# Sheet.net
KiCad netlist of a schematic drawn in Altium Designer
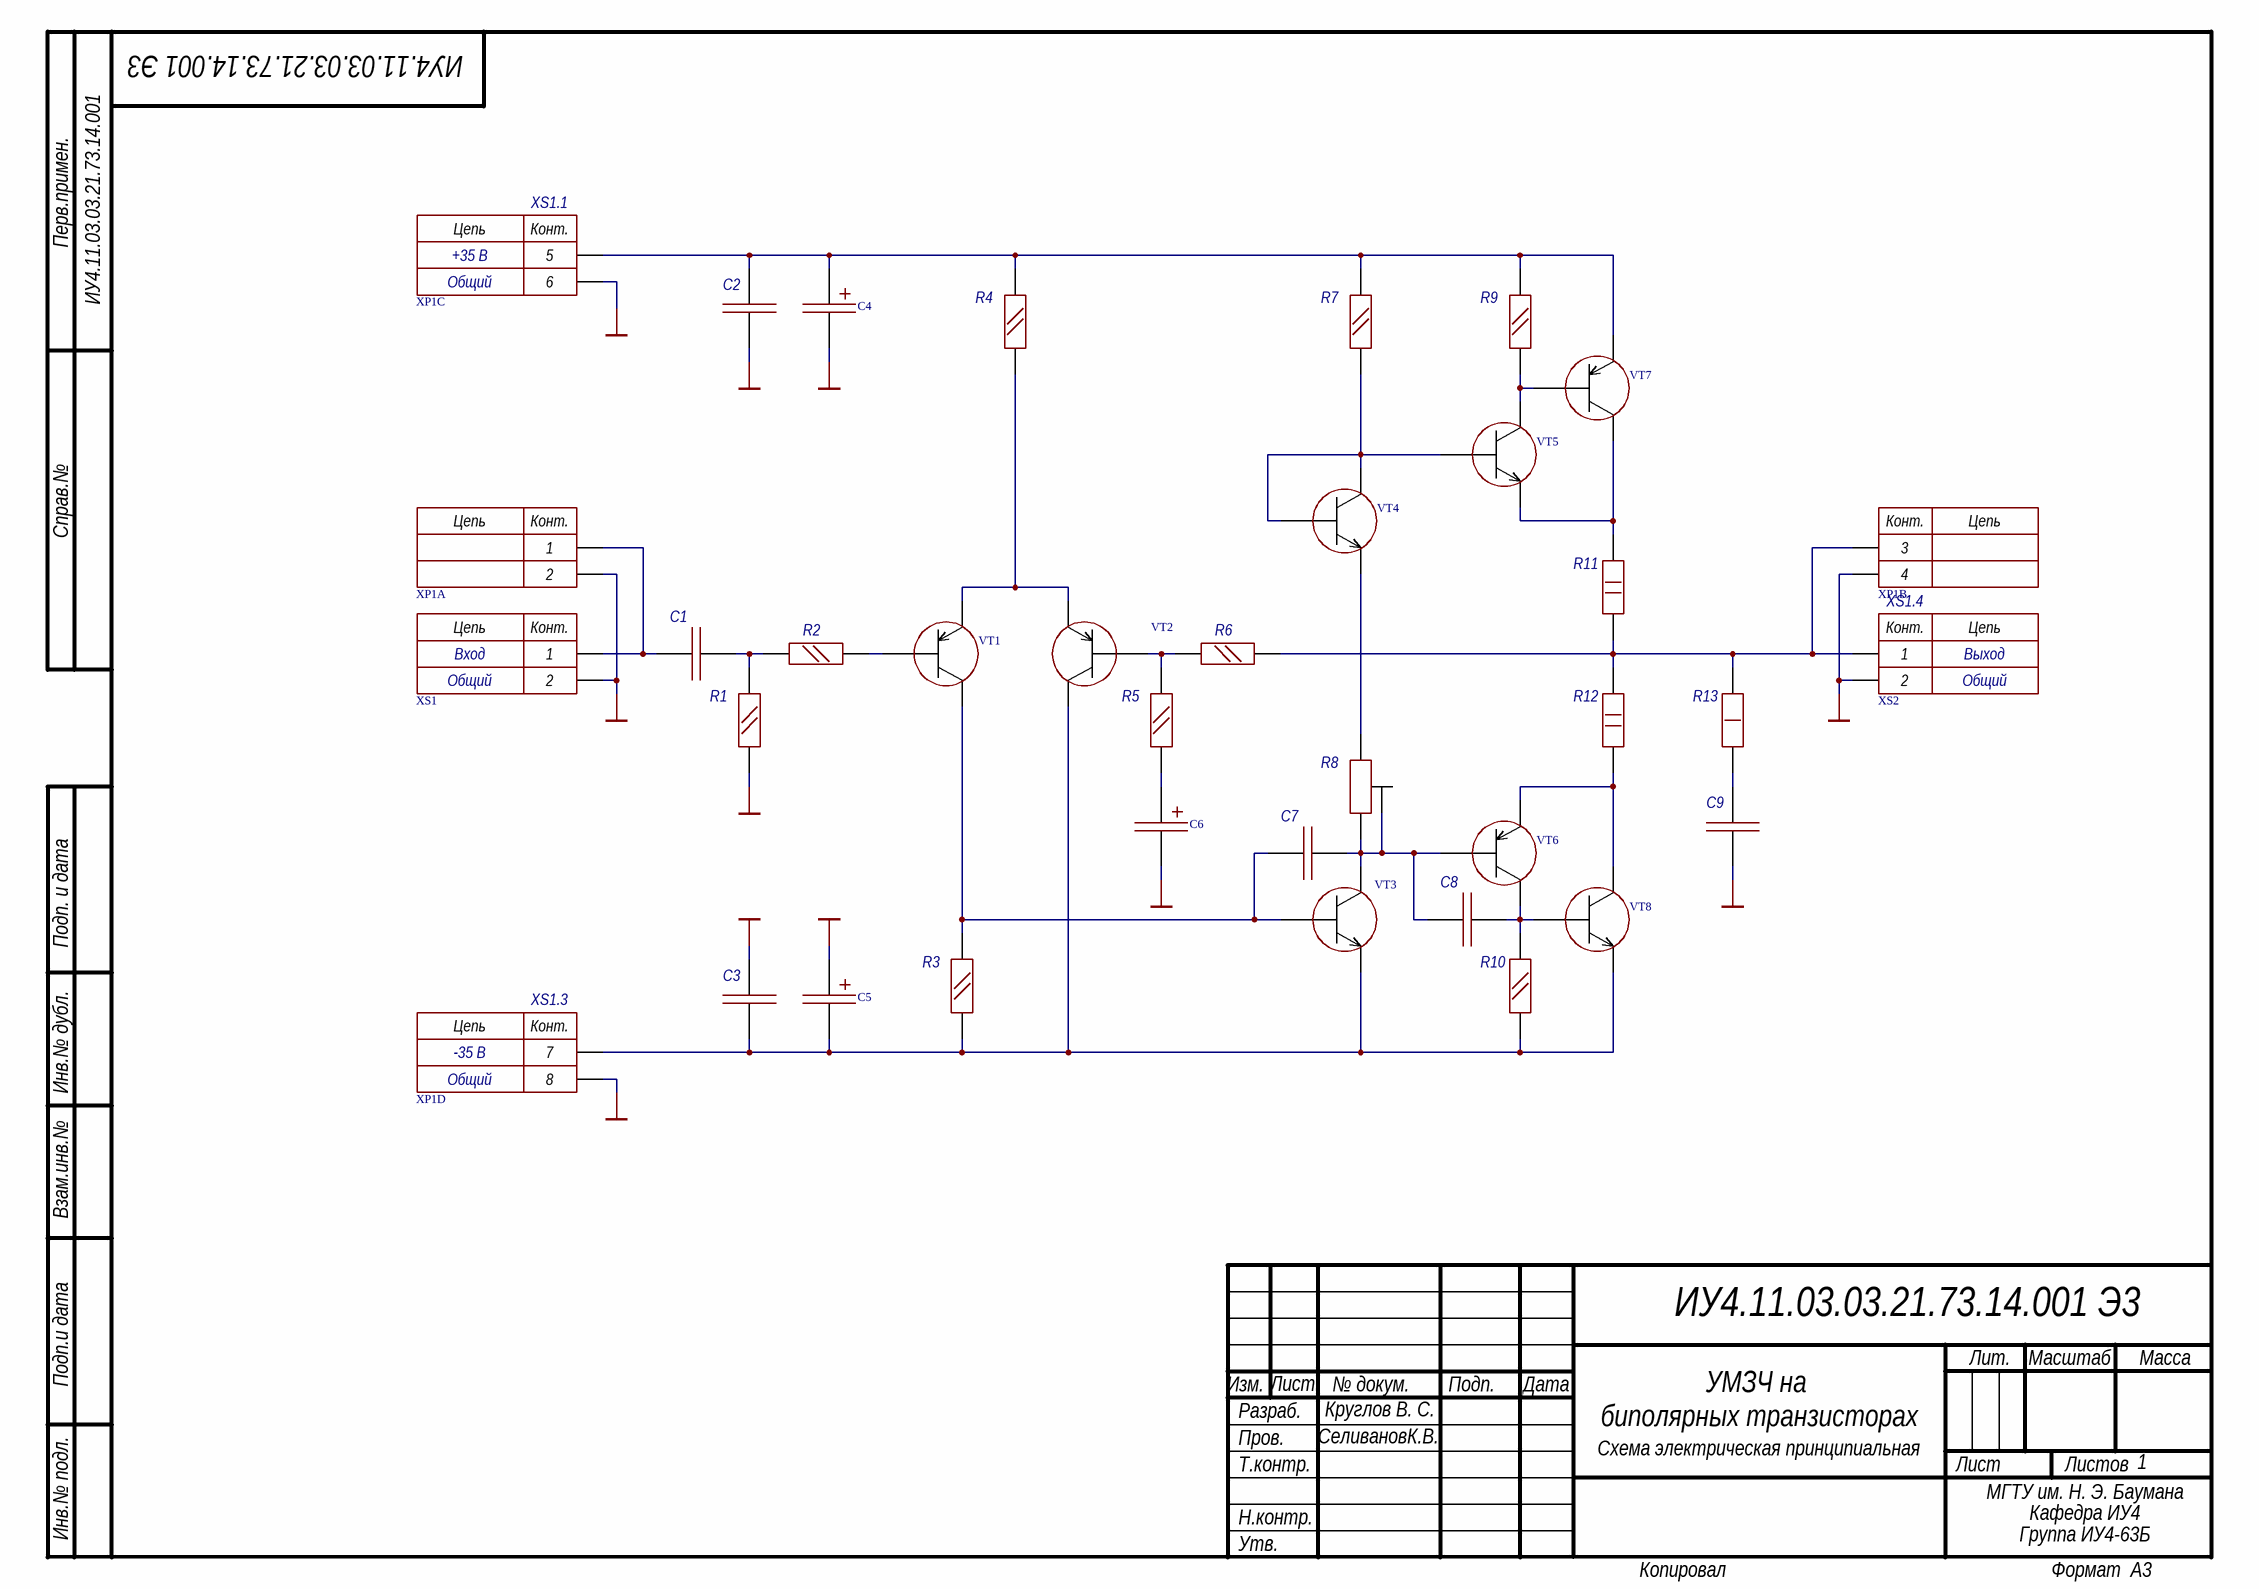
[diagram p0: Sheet.SchDoc]

(export (version "E")
  (design (tool "Eeschema 10.0.6"))
  (components
    (comp (ref "C1")
      (value "Capacitor")
      (footprint "C_PLY_10X5")
      (libsource (lib "Components - 07.07.24 - 20.56") (part "Capacitor"))
    )
    (comp (ref "C2")
      (value "Capacitor")
      (footprint "C_PLY_10X5")
      (libsource (lib "Components - 07.07.24 - 20.56") (part "Capacitor"))
    )
    (comp (ref "C3")
      (value "Capacitor")
      (footprint "C_PLY_10X5")
      (libsource (lib "Components - 07.07.24 - 20.56") (part "Capacitor"))
    )
    (comp (ref "C4")
      (value "Capactor polar")
      (footprint "C_EL_12X25")
      (libsource (lib "Components - 07.07.24 - 20.56") (part "Capactor polar"))
    )
    (comp (ref "C5")
      (value "Capactor polar")
      (footprint "C_EL_12X25")
      (libsource (lib "Components - 07.07.24 - 20.56") (part "Capactor polar"))
    )
    (comp (ref "C6")
      (value "Capactor polar")
      (footprint "C_EL_4X7")
      (libsource (lib "Components - 07.07.24 - 20.56") (part "Capactor polar"))
    )
    (comp (ref "C7")
      (value "Capacitor")
      (footprint "C_PLY_7X5")
      (libsource (lib "Components - 07.07.24 - 20.56") (part "Capacitor"))
    )
    (comp (ref "C8")
      (value "Capacitor")
      (footprint "C_PLY_7X5")
      (libsource (lib "Components - 07.07.24 - 20.56") (part "Capacitor"))
    )
    (comp (ref "C9")
      (value "Capacitor")
      (footprint "C_PLY_10X5")
      (libsource (lib "Components - 07.07.24 - 20.56") (part "Capacitor"))
    )
    (comp (ref "R1")
      (value "Res")
      (footprint "R0125W_AX025")
      (libsource (lib "Integrated_Library_PAAF") (part "Res"))
    )
    (comp (ref "R2") (value "Res") (footprint "R0125W_AX025") (libsource (lib "") (part "Res_1")))
    (comp (ref "R3")
      (value "Res")
      (footprint "R0125W_AX025")
      (libsource (lib "Integrated_Library_PAAF") (part "Res"))
    )
    (comp (ref "R4")
      (value "Res")
      (footprint "R0125W_AX025")
      (libsource (lib "Integrated_Library_PAAF") (part "Res"))
    )
    (comp (ref "R5")
      (value "Res")
      (footprint "R0125W_AX025")
      (libsource (lib "Integrated_Library_PAAF") (part "Res"))
    )
    (comp (ref "R6") (value "Res") (footprint "R0125W_AX025") (libsource (lib "") (part "Res_1")))
    (comp (ref "R7")
      (value "Res")
      (footprint "R0125W_AX025")
      (libsource (lib "Integrated_Library_PAAF") (part "Res"))
    )
    (comp (ref "R8")
      (value "POT")
      (footprint "POT_3296W")
      (libsource (lib "Integrated_Library_PAAF") (part "POT"))
    )
    (comp (ref "R9")
      (value "Res")
      (footprint "R0125W_AX025")
      (libsource (lib "Integrated_Library_PAAF") (part "Res"))
    )
    (comp (ref "R10")
      (value "Res")
      (footprint "R0125W_AX025")
      (libsource (lib "Integrated_Library_PAAF") (part "Res"))
    )
    (comp (ref "R11")
      (value "Res")
      (footprint "R2W_AX08")
      (libsource (lib "Integrated_Library_PAAF") (part "Res"))
    )
    (comp (ref "R12")
      (value "Res")
      (footprint "R2W_AX08")
      (libsource (lib "Integrated_Library_PAAF") (part "Res"))
    )
    (comp (ref "R13")
      (value "Res")
      (footprint "R1W_AX06")
      (libsource (lib "Integrated_Library_PAAF") (part "Res"))
    )
    (comp (ref "VT1")
      (value "Transistor_PNP")
      (footprint "TO92_3")
      (libsource (lib "Components - 07.07.24 - 21.07") (part "Transistor_PNP"))
    )
    (comp (ref "VT2")
      (value "Transistor_PNP")
      (footprint "TO92_3")
      (libsource (lib "Components - 07.07.24 - 21.07") (part "Transistor_PNP"))
    )
    (comp (ref "VT3")
      (value "BD139G")
      (footprint "TO220_3")
      (libsource (lib "Components - 07.07.24 - 21.07") (part "Transistor_NPN"))
    )
    (comp (ref "VT4")
      (value "BD139G")
      (footprint "TO126_3")
      (libsource (lib "Components - 07.07.24 - 21.07") (part "Transistor_NPN"))
    )
    (comp (ref "VT5")
      (value "BD139G")
      (footprint "TO126_3")
      (libsource (lib "Components - 07.07.24 - 21.07") (part "Transistor_NPN"))
    )
    (comp (ref "VT6")
      (value "Transistor_PNP")
      (footprint "TO126_3")
      (libsource (lib "Components - 07.07.24 - 21.07") (part "Transistor_PNP"))
    )
    (comp (ref "VT7")
      (value "Transistor_PNP")
      (footprint "TO247_3")
      (libsource (lib "Components - 07.07.24 - 21.07") (part "Transistor_PNP"))
    )
    (comp (ref "VT8")
      (value "BD139G")
      (footprint "TO247_3")
      (libsource (lib "Components - 07.07.24 - 21.07") (part "Transistor_NPN"))
    )
    (comp (ref "XP1")
      (value "CONN")
      (footprint "HDRR_F_2X4")
      (libsource (lib "Components - 07.07.24 - 20.56") (part "CONN"))
    )
    (comp (ref "XS1")
      (value "Audio")
      (footprint "FP-NMJ4HFD2-MFG")
      (libsource (lib "Integrated_Library_PAAF") (part "Audio"))
    )
    (comp (ref "XS2")
      (value "Audio")
      (footprint "FP-NMJ4HFD2-MFG")
      (libsource (lib "Integrated_Library_PAAF") (part "Audio"))
    )
  )
  (nets
    (net (code "1") (name "GND") (class "Default")
      (node (ref "C2") (pin "2") (pinfunction "2_2") (pintype "passive"))
      (node (ref "C3") (pin "2") (pinfunction "2_2") (pintype "passive"))
      (node (ref "C4") (pin "1") (pinfunction "1_1") (pintype "passive"))
      (node (ref "C5") (pin "2") (pinfunction "2_2") (pintype "passive"))
      (node (ref "C6") (pin "1") (pinfunction "1_1") (pintype "passive"))
      (node (ref "C9") (pin "2") (pinfunction "2_2") (pintype "passive"))
      (node (ref "R1") (pin "1") (pinfunction "1_1") (pintype "passive"))
      (node (ref "XP1") (pin "2") (pintype "passive"))
      (node (ref "XP1") (pin "4") (pintype "passive"))
      (node (ref "XP1") (pin "6") (pintype "passive"))
      (node (ref "XP1") (pin "8") (pintype "passive"))
      (node (ref "XS1") (pin "2") (pintype "passive"))
      (node (ref "XS2") (pin "2") (pintype "passive"))
    )
    (net (code "2") (name "Net-(C1-Pad1)") (class "Default")
      (node (ref "C1") (pin "1") (pinfunction "1_1") (pintype "passive"))
      (node (ref "XP1") (pin "1") (pintype "passive"))
      (node (ref "XS1") (pin "1") (pintype "passive"))
    )
    (net (code "3") (name "Net-(C1-Pad2)") (class "Default")
      (node (ref "C1") (pin "2") (pinfunction "2_2") (pintype "passive"))
      (node (ref "R1") (pin "2") (pinfunction "2_2") (pintype "passive"))
      (node (ref "R2") (pin "2") (pinfunction "2_2") (pintype "passive"))
    )
    (net (code "4") (name "Net-(C6-Pad2)") (class "Default")
      (node (ref "C6") (pin "2") (pinfunction "2_2") (pintype "passive"))
      (node (ref "R5") (pin "1") (pinfunction "1_1") (pintype "passive"))
    )
    (net (code "5") (name "Net-(C9-Pad1)") (class "Default")
      (node (ref "C9") (pin "1") (pinfunction "1_1") (pintype "passive"))
      (node (ref "R13") (pin "1") (pinfunction "1_1") (pintype "passive"))
    )
    (net (code "6") (name "Net-(R11-Pad1)") (class "Default")
      (node (ref "R11") (pin "1") (pinfunction "1_1") (pintype "passive"))
      (node (ref "R12") (pin "2") (pinfunction "2_2") (pintype "passive"))
      (node (ref "R13") (pin "2") (pinfunction "2_2") (pintype "passive"))
      (node (ref "R6") (pin "1") (pinfunction "1_1") (pintype "passive"))
      (node (ref "XP1") (pin "3") (pintype "passive"))
      (node (ref "XS2") (pin "1") (pintype "passive"))
    )
    (net (code "7") (name "Net-(VT1-B)") (class "Default")
      (node (ref "R2") (pin "1") (pinfunction "1_1") (pintype "passive"))
      (node (ref "VT1") (pin "3") (pinfunction "B_3") (pintype "passive"))
    )
    (net (code "8") (name "Net-(VT1-C)") (class "Default")
      (node (ref "C7") (pin "1") (pinfunction "1_1") (pintype "passive"))
      (node (ref "R3") (pin "2") (pinfunction "2_2") (pintype "passive"))
      (node (ref "VT1") (pin "2") (pinfunction "C_2") (pintype "passive"))
      (node (ref "VT3") (pin "3") (pinfunction "B_3") (pintype "passive"))
    )
    (net (code "9") (name "Net-(VT1-E)") (class "Default")
      (node (ref "R4") (pin "1") (pinfunction "1_1") (pintype "passive"))
      (node (ref "VT1") (pin "1") (pinfunction "E_1") (pintype "passive"))
      (node (ref "VT2") (pin "1") (pinfunction "E_1") (pintype "passive"))
    )
    (net (code "10") (name "Net-(VT2-B)") (class "Default")
      (node (ref "R5") (pin "2") (pinfunction "2_2") (pintype "passive"))
      (node (ref "R6") (pin "2") (pinfunction "2_2") (pintype "passive"))
      (node (ref "VT2") (pin "3") (pinfunction "B_3") (pintype "passive"))
    )
    (net (code "11") (name "Net-(VT2-C)") (class "Default")
      (node (ref "C3") (pin "1") (pinfunction "1_1") (pintype "passive"))
      (node (ref "C5") (pin "1") (pinfunction "1_1") (pintype "passive"))
      (node (ref "R10") (pin "1") (pinfunction "1_1") (pintype "passive"))
      (node (ref "R3") (pin "1") (pinfunction "1_1") (pintype "passive"))
      (node (ref "VT2") (pin "2") (pinfunction "C_2") (pintype "passive"))
      (node (ref "VT3") (pin "1") (pinfunction "E_1") (pintype "passive"))
      (node (ref "VT8") (pin "1") (pinfunction "E_1") (pintype "passive"))
      (node (ref "XP1") (pin "7") (pintype "passive"))
    )
    (net (code "12") (name "Net-(VT3-C)") (class "Default")
      (node (ref "C7") (pin "2") (pinfunction "2_2") (pintype "passive"))
      (node (ref "C8") (pin "1") (pinfunction "1_1") (pintype "passive"))
      (node (ref "R8") (pin "2") (pinfunction "2_2") (pintype "passive"))
      (node (ref "R8") (pin "3") (pinfunction "3_3") (pintype "passive"))
      (node (ref "VT3") (pin "2") (pinfunction "C_2") (pintype "passive"))
      (node (ref "VT6") (pin "3") (pinfunction "B_3") (pintype "passive"))
    )
    (net (code "13") (name "Net-(VT4-B)") (class "Default")
      (node (ref "R7") (pin "1") (pinfunction "1_1") (pintype "passive"))
      (node (ref "VT4") (pin "2") (pinfunction "C_2") (pintype "passive"))
      (node (ref "VT4") (pin "3") (pinfunction "B_3") (pintype "passive"))
      (node (ref "VT5") (pin "3") (pinfunction "B_3") (pintype "passive"))
    )
    (net (code "14") (name "Net-(VT4-E)") (class "Default")
      (node (ref "R8") (pin "1") (pinfunction "1_1") (pintype "passive"))
      (node (ref "VT4") (pin "1") (pinfunction "E_1") (pintype "passive"))
    )
    (net (code "15") (name "Net-(VT5-C)") (class "Default")
      (node (ref "R9") (pin "1") (pinfunction "1_1") (pintype "passive"))
      (node (ref "VT5") (pin "2") (pinfunction "C_2") (pintype "passive"))
      (node (ref "VT7") (pin "3") (pinfunction "B_3") (pintype "passive"))
    )
    (net (code "16") (name "Net-(VT5-E)") (class "Default")
      (node (ref "R11") (pin "2") (pinfunction "2_2") (pintype "passive"))
      (node (ref "VT5") (pin "1") (pinfunction "E_1") (pintype "passive"))
      (node (ref "VT7") (pin "2") (pinfunction "C_2") (pintype "passive"))
    )
    (net (code "17") (name "Net-(VT6-C)") (class "Default")
      (node (ref "C8") (pin "2") (pinfunction "2_2") (pintype "passive"))
      (node (ref "R10") (pin "2") (pinfunction "2_2") (pintype "passive"))
      (node (ref "VT6") (pin "2") (pinfunction "C_2") (pintype "passive"))
      (node (ref "VT8") (pin "3") (pinfunction "B_3") (pintype "passive"))
    )
    (net (code "18") (name "Net-(VT6-E)") (class "Default")
      (node (ref "R12") (pin "1") (pinfunction "1_1") (pintype "passive"))
      (node (ref "VT6") (pin "1") (pinfunction "E_1") (pintype "passive"))
      (node (ref "VT8") (pin "2") (pinfunction "C_2") (pintype "passive"))
    )
    (net (code "19") (name "Net-(VT7-E)") (class "Default")
      (node (ref "C2") (pin "1") (pinfunction "1_1") (pintype "passive"))
      (node (ref "C4") (pin "2") (pinfunction "2_2") (pintype "passive"))
      (node (ref "R4") (pin "2") (pinfunction "2_2") (pintype "passive"))
      (node (ref "R7") (pin "2") (pinfunction "2_2") (pintype "passive"))
      (node (ref "R9") (pin "2") (pinfunction "2_2") (pintype "passive"))
      (node (ref "VT7") (pin "1") (pinfunction "E_1") (pintype "passive"))
      (node (ref "XP1") (pin "5") (pintype "passive"))
    )
  )
)
